# wifi_smart_controller.net
KiCad netlist of a schematic drawn in EasyEDA Pro
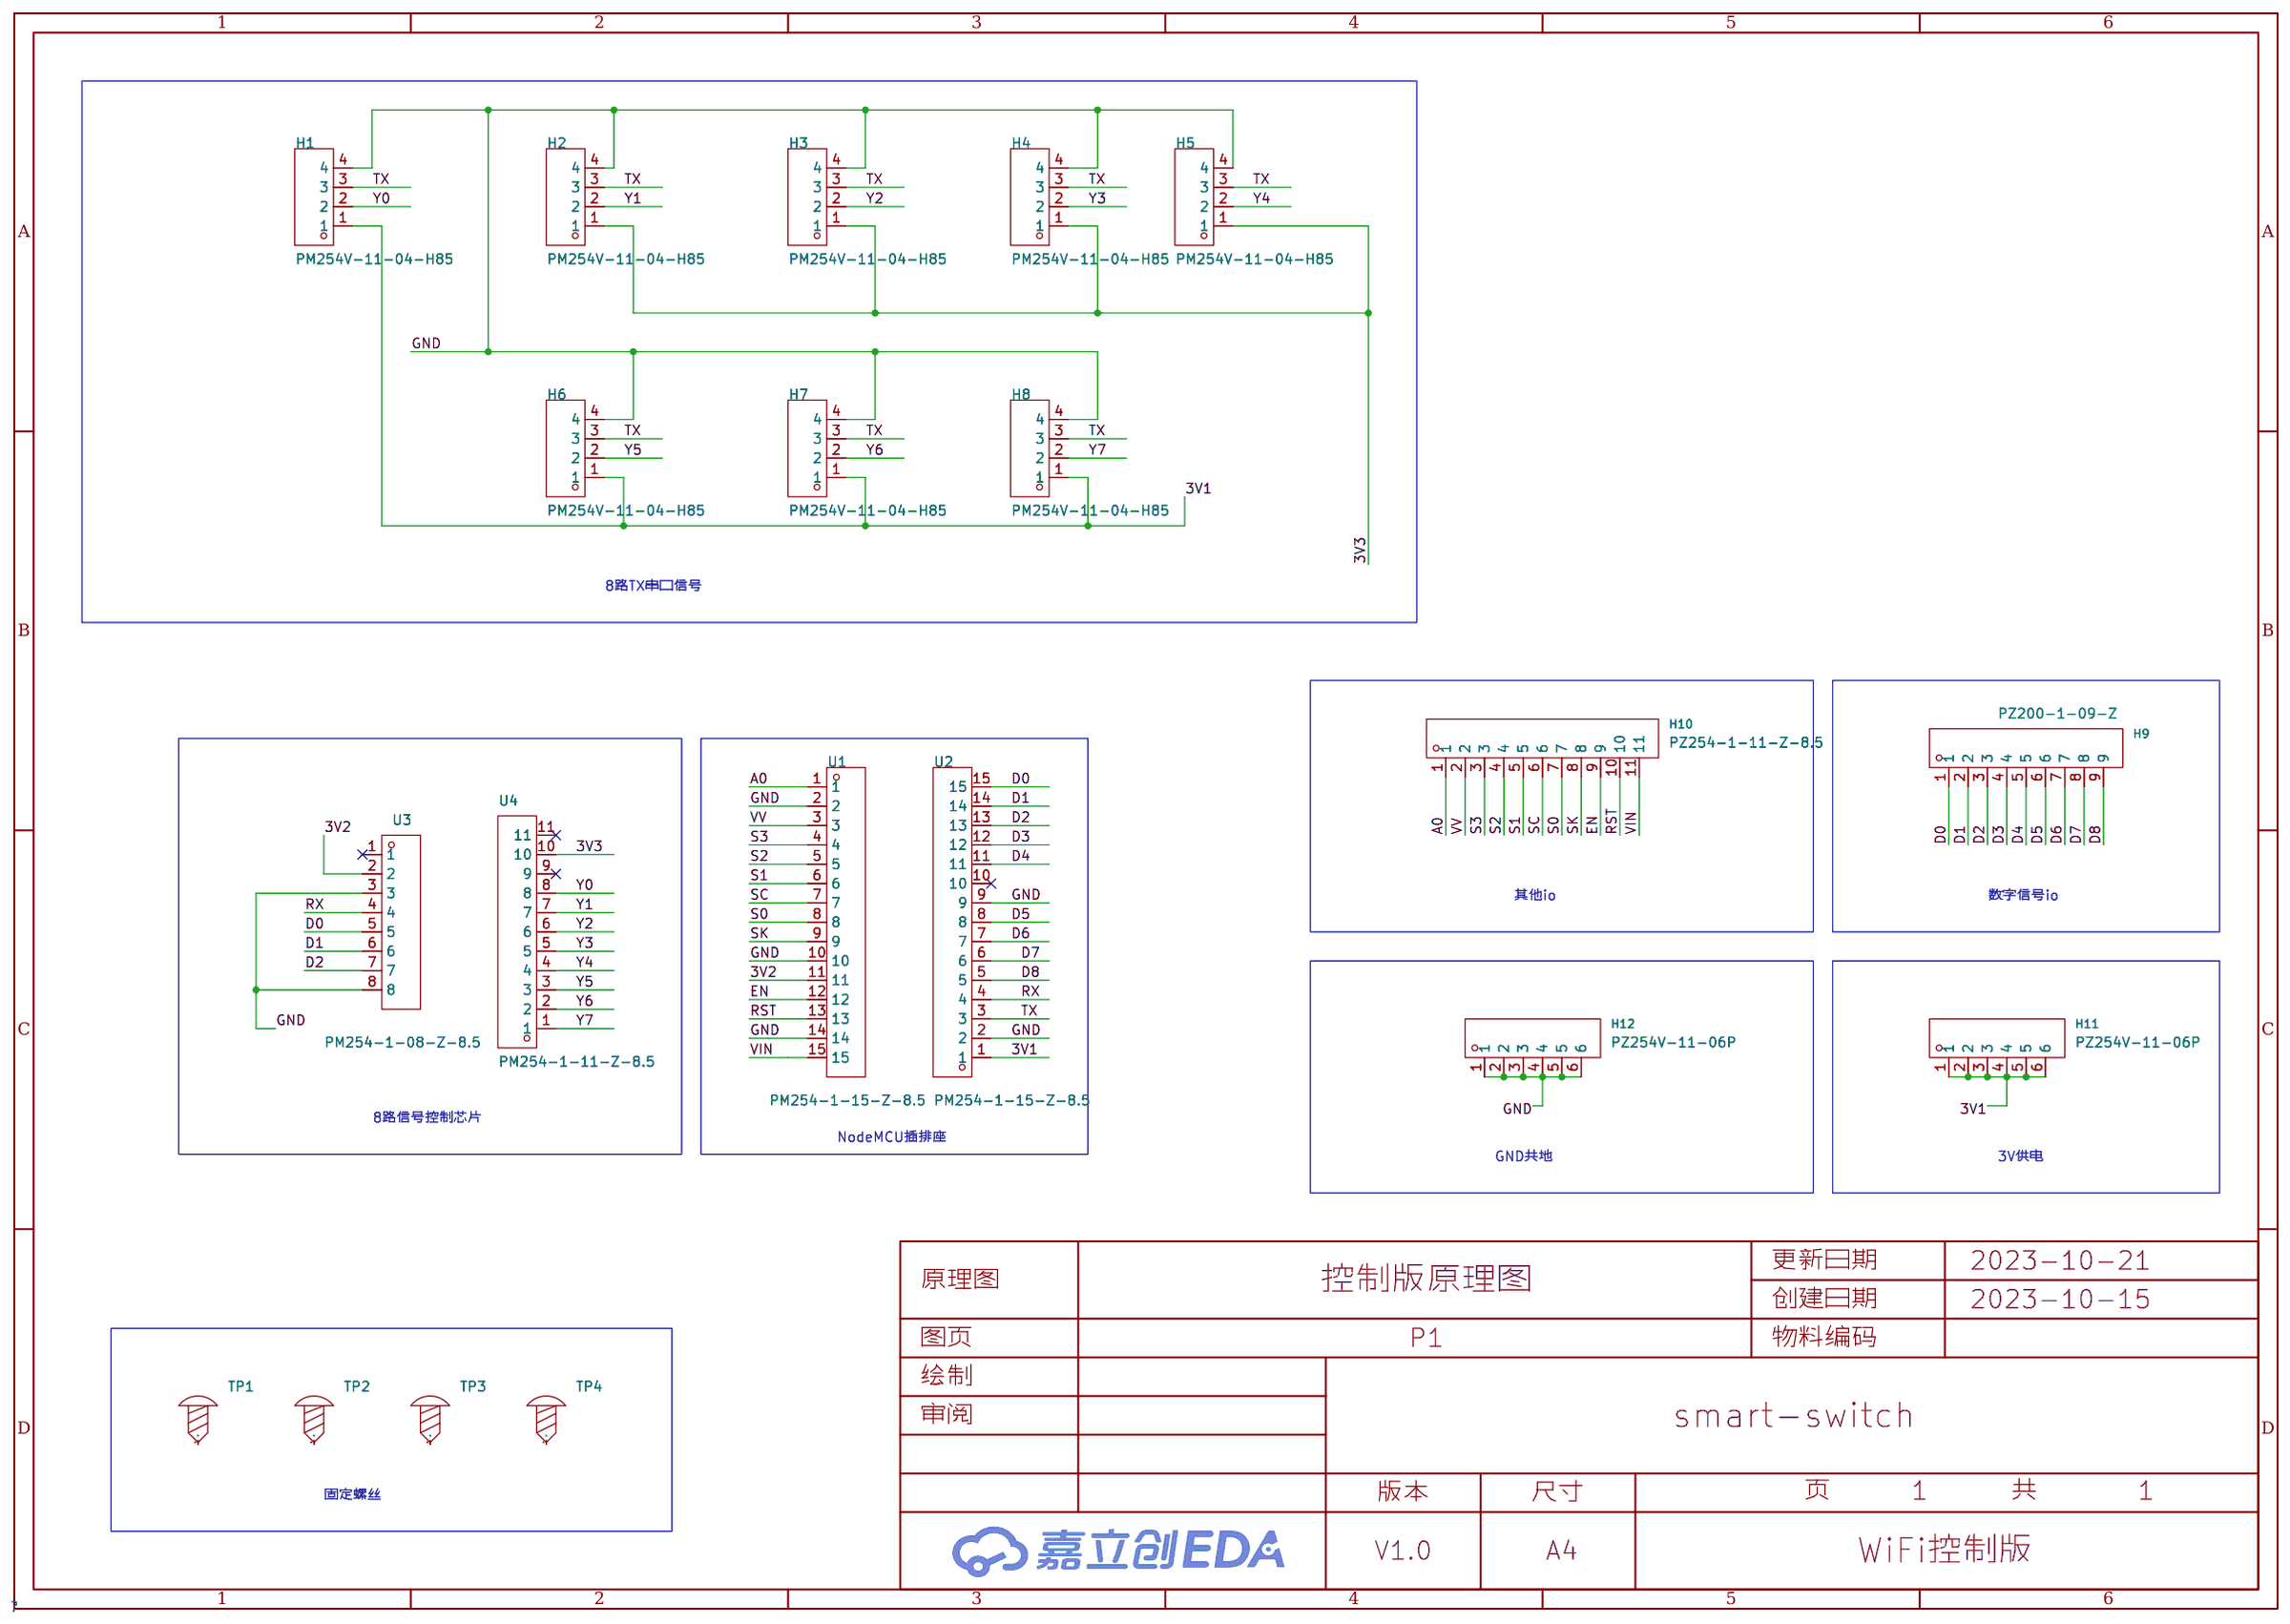
[diagram p0: schematic sheet]

(export (version "E")
  (design (tool "Eeschema 10.0.6"))
  (components
    (comp (ref "H1")
      (value "PM254V-11-04-H85")
      (footprint "easyedapro:HDR-TH_4P-P2.54-V-F")
      (description "排数:单排;总孔位数:4P;间距:2.54mm;插孔结构:1x4P;行距:-;安装类型:直插;塑高:-;触头材质:黄铜;触头镀层:-;")
      (fields (field (name "Manufacturer") "XFCN(兴飞)"))
      (libsource (lib "easyedapro") (part "PM254V-11-04-H85"))
    )
    (comp (ref "H2")
      (value "PM254V-11-04-H85")
      (footprint "easyedapro:HDR-TH_4P-P2.54-V-F")
      (description "排数:单排;总孔位数:4P;间距:2.54mm;插孔结构:1x4P;行距:-;安装类型:直插;塑高:-;触头材质:黄铜;触头镀层:-;")
      (fields (field (name "Manufacturer") "XFCN(兴飞)"))
      (libsource (lib "easyedapro") (part "PM254V-11-04-H85"))
    )
    (comp (ref "H3")
      (value "PM254V-11-04-H85")
      (footprint "easyedapro:HDR-TH_4P-P2.54-V-F")
      (description "排数:单排;总孔位数:4P;间距:2.54mm;插孔结构:1x4P;行距:-;安装类型:直插;塑高:-;触头材质:黄铜;触头镀层:-;")
      (fields (field (name "Manufacturer") "XFCN(兴飞)"))
      (libsource (lib "easyedapro") (part "PM254V-11-04-H85"))
    )
    (comp (ref "H4")
      (value "PM254V-11-04-H85")
      (footprint "easyedapro:HDR-TH_4P-P2.54-V-F")
      (description "排数:单排;总孔位数:4P;间距:2.54mm;插孔结构:1x4P;行距:-;安装类型:直插;塑高:-;触头材质:黄铜;触头镀层:-;")
      (fields (field (name "Manufacturer") "XFCN(兴飞)"))
      (libsource (lib "easyedapro") (part "PM254V-11-04-H85"))
    )
    (comp (ref "H5")
      (value "PM254V-11-04-H85")
      (footprint "easyedapro:HDR-TH_4P-P2.54-V-F")
      (description "排数:单排;总孔位数:4P;间距:2.54mm;插孔结构:1x4P;行距:-;安装类型:直插;塑高:-;触头材质:黄铜;触头镀层:-;")
      (fields (field (name "Manufacturer") "XFCN(兴飞)"))
      (libsource (lib "easyedapro") (part "PM254V-11-04-H85"))
    )
    (comp (ref "H6")
      (value "PM254V-11-04-H85")
      (footprint "easyedapro:HDR-TH_4P-P2.54-V-F")
      (description "排数:单排;总孔位数:4P;间距:2.54mm;插孔结构:1x4P;行距:-;安装类型:直插;塑高:-;触头材质:黄铜;触头镀层:-;")
      (fields (field (name "Manufacturer") "XFCN(兴飞)"))
      (libsource (lib "easyedapro") (part "PM254V-11-04-H85"))
    )
    (comp (ref "H7")
      (value "PM254V-11-04-H85")
      (footprint "easyedapro:HDR-TH_4P-P2.54-V-F")
      (description "排数:单排;总孔位数:4P;间距:2.54mm;插孔结构:1x4P;行距:-;安装类型:直插;塑高:-;触头材质:黄铜;触头镀层:-;")
      (fields (field (name "Manufacturer") "XFCN(兴飞)"))
      (libsource (lib "easyedapro") (part "PM254V-11-04-H85"))
    )
    (comp (ref "H8")
      (value "PM254V-11-04-H85")
      (footprint "easyedapro:HDR-TH_4P-P2.54-V-F")
      (description "排数:单排;总孔位数:4P;间距:2.54mm;插孔结构:1x4P;行距:-;安装类型:直插;塑高:-;触头材质:黄铜;触头镀层:-;")
      (fields (field (name "Manufacturer") "XFCN(兴飞)"))
      (libsource (lib "easyedapro") (part "PM254V-11-04-H85"))
    )
    (comp (ref "H9")
      (value "PZ200-1-09-Z")
      (footprint "easyedapro:HDR-TH_9P-P2.00-V-M")
      (fields (field (name "Manufacturer") "HCTL(华灿天禄)"))
      (libsource (lib "easyedapro") (part "PZ200-1-09-Z"))
    )
    (comp (ref "H10")
      (value "PZ254-1-11-Z-8.5")
      (footprint "easyedapro:HDR-TH_11P-P2.54-V-M")
      (fields (field (name "Manufacturer") "HCTL(华灿天禄)"))
      (libsource (lib "easyedapro") (part "PZ254-1-11-Z-8.5"))
    )
    (comp (ref "H11")
      (value "PZ254V-11-06P")
      (footprint "easyedapro:HDR-TH_6P-P2.54-V-M")
      (fields (field (name "Manufacturer") "XFCN(兴飞)"))
      (libsource (lib "easyedapro") (part "PZ254V-11-06P"))
    )
    (comp (ref "H12")
      (value "PZ254V-11-06P")
      (footprint "easyedapro:HDR-TH_6P-P2.54-V-M")
      (fields (field (name "Manufacturer") "XFCN(兴飞)"))
      (libsource (lib "easyedapro") (part "PZ254V-11-06P"))
    )
    (comp (ref "TP1") (value "~") (footprint "easyedapro:M2螺丝") (libsource (lib "easyedapro") (part "螺丝孔")))
    (comp (ref "TP2") (value "~") (footprint "easyedapro:M2螺丝") (libsource (lib "easyedapro") (part "螺丝孔")))
    (comp (ref "TP3") (value "~") (footprint "easyedapro:M2螺丝") (libsource (lib "easyedapro") (part "螺丝孔")))
    (comp (ref "TP4") (value "~") (footprint "easyedapro:M2螺丝") (libsource (lib "easyedapro") (part "螺丝孔")))
    (comp (ref "U1")
      (value "PM254-1-15-Z-8.5")
      (footprint "easyedapro:HDR-TH_15P-P2.54-V-F")
      (fields (field (name "Manufacturer") "HCTL(华灿天禄)"))
      (libsource (lib "easyedapro") (part "PM254-1-15-Z-8.5"))
    )
    (comp (ref "U2")
      (value "PM254-1-15-Z-8.5")
      (footprint "easyedapro:HDR-TH_15P-P2.54-V-F")
      (fields (field (name "Manufacturer") "HCTL(华灿天禄)"))
      (libsource (lib "easyedapro") (part "PM254-1-15-Z-8.5"))
    )
    (comp (ref "U3")
      (value "PM254-1-08-Z-8.5")
      (footprint "easyedapro:HDR-TH_8P-P2.54-V-F")
      (fields (field (name "Manufacturer") "HCTL(华灿天禄)"))
      (libsource (lib "easyedapro") (part "PM254-1-08-Z-8.5"))
    )
    (comp (ref "U4")
      (value "PM254-1-11-Z-8.5")
      (footprint "easyedapro:HDR-TH_11P-P2.54-V-F")
      (fields (field (name "Manufacturer") "HCTL(华灿天禄)"))
      (libsource (lib "easyedapro") (part "PM254-1-11-Z-8.5"))
    )
  )
  (nets
    (net (code "1") (name "/3V1") (class "Default")
      (node (ref "H1") (pin "1") (pinfunction "1_1") (pintype "unspecified"))
      (node (ref "H11") (pin "1") (pinfunction "1_1") (pintype "input"))
      (node (ref "H11") (pin "2") (pinfunction "2_2") (pintype "input"))
      (node (ref "H11") (pin "3") (pinfunction "3_3") (pintype "input"))
      (node (ref "H11") (pin "4") (pinfunction "4_4") (pintype "input"))
      (node (ref "H11") (pin "5") (pinfunction "5_5") (pintype "input"))
      (node (ref "H11") (pin "6") (pinfunction "6_6") (pintype "input"))
      (node (ref "H6") (pin "1") (pinfunction "1_1") (pintype "unspecified"))
      (node (ref "H7") (pin "1") (pinfunction "1_1") (pintype "unspecified"))
      (node (ref "H8") (pin "1") (pinfunction "1_1") (pintype "unspecified"))
      (node (ref "U2") (pin "1") (pinfunction "1_1") (pintype "unspecified"))
    )
    (net (code "2") (name "/3V2") (class "Default")
      (node (ref "U1") (pin "11") (pinfunction "11_11") (pintype "unspecified"))
      (node (ref "U3") (pin "2") (pinfunction "2_2") (pintype "unspecified"))
    )
    (net (code "3") (name "/3V3") (class "Default")
      (node (ref "H2") (pin "1") (pinfunction "1_1") (pintype "unspecified"))
      (node (ref "H3") (pin "1") (pinfunction "1_1") (pintype "unspecified"))
      (node (ref "H4") (pin "1") (pinfunction "1_1") (pintype "unspecified"))
      (node (ref "H5") (pin "1") (pinfunction "1_1") (pintype "unspecified"))
      (node (ref "U4") (pin "10") (pinfunction "10_10") (pintype "unspecified"))
    )
    (net (code "4") (name "/A0") (class "Default")
      (node (ref "H10") (pin "1") (pinfunction "1_1") (pintype "input"))
      (node (ref "U1") (pin "1") (pinfunction "1_1") (pintype "unspecified"))
    )
    (net (code "5") (name "/D0") (class "Default")
      (node (ref "H9") (pin "1") (pinfunction "1_1") (pintype "input"))
      (node (ref "U2") (pin "15") (pinfunction "15_15") (pintype "unspecified"))
      (node (ref "U3") (pin "5") (pinfunction "5_5") (pintype "unspecified"))
    )
    (net (code "6") (name "/D1") (class "Default")
      (node (ref "H9") (pin "2") (pinfunction "2_2") (pintype "input"))
      (node (ref "U2") (pin "14") (pinfunction "14_14") (pintype "unspecified"))
      (node (ref "U3") (pin "6") (pinfunction "6_6") (pintype "unspecified"))
    )
    (net (code "7") (name "/D2") (class "Default")
      (node (ref "H9") (pin "3") (pinfunction "3_3") (pintype "input"))
      (node (ref "U2") (pin "13") (pinfunction "13_13") (pintype "unspecified"))
      (node (ref "U3") (pin "7") (pinfunction "7_7") (pintype "unspecified"))
    )
    (net (code "8") (name "/D3") (class "Default")
      (node (ref "H9") (pin "4") (pinfunction "4_4") (pintype "input"))
      (node (ref "U2") (pin "12") (pinfunction "12_12") (pintype "unspecified"))
    )
    (net (code "9") (name "/D4") (class "Default")
      (node (ref "H9") (pin "5") (pinfunction "5_5") (pintype "input"))
      (node (ref "U2") (pin "11") (pinfunction "11_11") (pintype "unspecified"))
    )
    (net (code "10") (name "/D5") (class "Default")
      (node (ref "H9") (pin "6") (pinfunction "6_6") (pintype "input"))
      (node (ref "U2") (pin "8") (pinfunction "8_8") (pintype "unspecified"))
    )
    (net (code "11") (name "/D6") (class "Default")
      (node (ref "H9") (pin "7") (pinfunction "7_7") (pintype "input"))
      (node (ref "U2") (pin "7") (pinfunction "7_7") (pintype "unspecified"))
    )
    (net (code "12") (name "/D7") (class "Default")
      (node (ref "H9") (pin "8") (pinfunction "8_8") (pintype "input"))
      (node (ref "U2") (pin "6") (pinfunction "6_6") (pintype "unspecified"))
    )
    (net (code "13") (name "/D8") (class "Default")
      (node (ref "H9") (pin "9") (pinfunction "9_9") (pintype "input"))
      (node (ref "U2") (pin "5") (pinfunction "5_5") (pintype "unspecified"))
    )
    (net (code "14") (name "/EN") (class "Default")
      (node (ref "H10") (pin "9") (pinfunction "9_9") (pintype "input"))
      (node (ref "U1") (pin "12") (pinfunction "12_12") (pintype "unspecified"))
    )
    (net (code "15") (name "/GND") (class "Default")
      (node (ref "H1") (pin "4") (pinfunction "4_4") (pintype "unspecified"))
      (node (ref "H12") (pin "1") (pinfunction "1_1") (pintype "input"))
      (node (ref "H12") (pin "2") (pinfunction "2_2") (pintype "input"))
      (node (ref "H12") (pin "3") (pinfunction "3_3") (pintype "input"))
      (node (ref "H12") (pin "4") (pinfunction "4_4") (pintype "input"))
      (node (ref "H12") (pin "5") (pinfunction "5_5") (pintype "input"))
      (node (ref "H12") (pin "6") (pinfunction "6_6") (pintype "input"))
      (node (ref "H2") (pin "4") (pinfunction "4_4") (pintype "unspecified"))
      (node (ref "H3") (pin "4") (pinfunction "4_4") (pintype "unspecified"))
      (node (ref "H4") (pin "4") (pinfunction "4_4") (pintype "unspecified"))
      (node (ref "H5") (pin "4") (pinfunction "4_4") (pintype "unspecified"))
      (node (ref "H6") (pin "4") (pinfunction "4_4") (pintype "unspecified"))
      (node (ref "H7") (pin "4") (pinfunction "4_4") (pintype "unspecified"))
      (node (ref "H8") (pin "4") (pinfunction "4_4") (pintype "unspecified"))
      (node (ref "U1") (pin "10") (pinfunction "10_10") (pintype "unspecified"))
      (node (ref "U1") (pin "14") (pinfunction "14_14") (pintype "unspecified"))
      (node (ref "U1") (pin "2") (pinfunction "2_2") (pintype "unspecified"))
      (node (ref "U2") (pin "2") (pinfunction "2_2") (pintype "unspecified"))
      (node (ref "U2") (pin "9") (pinfunction "9_9") (pintype "unspecified"))
      (node (ref "U3") (pin "3") (pinfunction "3_3") (pintype "unspecified"))
      (node (ref "U3") (pin "8") (pinfunction "8_8") (pintype "unspecified"))
    )
    (net (code "16") (name "/RST") (class "Default")
      (node (ref "H10") (pin "10") (pinfunction "10_10") (pintype "input"))
      (node (ref "U1") (pin "13") (pinfunction "13_13") (pintype "unspecified"))
    )
    (net (code "17") (name "/RX") (class "Default")
      (node (ref "U2") (pin "4") (pinfunction "4_4") (pintype "unspecified"))
      (node (ref "U3") (pin "4") (pinfunction "4_4") (pintype "unspecified"))
    )
    (net (code "18") (name "/S0") (class "Default")
      (node (ref "H10") (pin "7") (pinfunction "7_7") (pintype "input"))
      (node (ref "U1") (pin "8") (pinfunction "8_8") (pintype "unspecified"))
    )
    (net (code "19") (name "/S1") (class "Default")
      (node (ref "H10") (pin "5") (pinfunction "5_5") (pintype "input"))
      (node (ref "U1") (pin "6") (pinfunction "6_6") (pintype "unspecified"))
    )
    (net (code "20") (name "/S2") (class "Default")
      (node (ref "H10") (pin "4") (pinfunction "4_4") (pintype "input"))
      (node (ref "U1") (pin "5") (pinfunction "5_5") (pintype "unspecified"))
    )
    (net (code "21") (name "/S3") (class "Default")
      (node (ref "H10") (pin "3") (pinfunction "3_3") (pintype "input"))
      (node (ref "U1") (pin "4") (pinfunction "4_4") (pintype "unspecified"))
    )
    (net (code "22") (name "/SC") (class "Default")
      (node (ref "H10") (pin "6") (pinfunction "6_6") (pintype "input"))
      (node (ref "U1") (pin "7") (pinfunction "7_7") (pintype "unspecified"))
    )
    (net (code "23") (name "/SK") (class "Default")
      (node (ref "H10") (pin "8") (pinfunction "8_8") (pintype "input"))
      (node (ref "U1") (pin "9") (pinfunction "9_9") (pintype "unspecified"))
    )
    (net (code "24") (name "/TX") (class "Default")
      (node (ref "H1") (pin "3") (pinfunction "3_3") (pintype "unspecified"))
      (node (ref "H2") (pin "3") (pinfunction "3_3") (pintype "unspecified"))
      (node (ref "H3") (pin "3") (pinfunction "3_3") (pintype "unspecified"))
      (node (ref "H4") (pin "3") (pinfunction "3_3") (pintype "unspecified"))
      (node (ref "H5") (pin "3") (pinfunction "3_3") (pintype "unspecified"))
      (node (ref "H6") (pin "3") (pinfunction "3_3") (pintype "unspecified"))
      (node (ref "H7") (pin "3") (pinfunction "3_3") (pintype "unspecified"))
      (node (ref "H8") (pin "3") (pinfunction "3_3") (pintype "unspecified"))
      (node (ref "U2") (pin "3") (pinfunction "3_3") (pintype "unspecified"))
    )
    (net (code "25") (name "/VIN") (class "Default")
      (node (ref "H10") (pin "11") (pinfunction "11_11") (pintype "input"))
      (node (ref "U1") (pin "15") (pinfunction "15_15") (pintype "unspecified"))
    )
    (net (code "26") (name "/VV") (class "Default")
      (node (ref "H10") (pin "2") (pinfunction "2_2") (pintype "input"))
      (node (ref "U1") (pin "3") (pinfunction "3_3") (pintype "unspecified"))
    )
    (net (code "27") (name "/Y0") (class "Default")
      (node (ref "H1") (pin "2") (pinfunction "2_2") (pintype "unspecified"))
      (node (ref "U4") (pin "8") (pinfunction "8_8") (pintype "unspecified"))
    )
    (net (code "28") (name "/Y1") (class "Default")
      (node (ref "H2") (pin "2") (pinfunction "2_2") (pintype "unspecified"))
      (node (ref "U4") (pin "7") (pinfunction "7_7") (pintype "unspecified"))
    )
    (net (code "29") (name "/Y2") (class "Default")
      (node (ref "H3") (pin "2") (pinfunction "2_2") (pintype "unspecified"))
      (node (ref "U4") (pin "6") (pinfunction "6_6") (pintype "unspecified"))
    )
    (net (code "30") (name "/Y3") (class "Default")
      (node (ref "H4") (pin "2") (pinfunction "2_2") (pintype "unspecified"))
      (node (ref "U4") (pin "5") (pinfunction "5_5") (pintype "unspecified"))
    )
    (net (code "31") (name "/Y4") (class "Default")
      (node (ref "H5") (pin "2") (pinfunction "2_2") (pintype "unspecified"))
      (node (ref "U4") (pin "4") (pinfunction "4_4") (pintype "unspecified"))
    )
    (net (code "32") (name "/Y5") (class "Default")
      (node (ref "H6") (pin "2") (pinfunction "2_2") (pintype "unspecified"))
      (node (ref "U4") (pin "3") (pinfunction "3_3") (pintype "unspecified"))
    )
    (net (code "33") (name "/Y6") (class "Default")
      (node (ref "H7") (pin "2") (pinfunction "2_2") (pintype "unspecified"))
      (node (ref "U4") (pin "2") (pinfunction "2_2") (pintype "unspecified"))
    )
    (net (code "34") (name "/Y7") (class "Default")
      (node (ref "H8") (pin "2") (pinfunction "2_2") (pintype "unspecified"))
      (node (ref "U4") (pin "1") (pinfunction "1_1") (pintype "unspecified"))
    )
    (net (code "35") (name "unconnected-(TP1-Pad1)") (class "Default")
      (node (ref "TP1") (pin "1") (pinfunction "1_1") (pintype "input"))
    )
    (net (code "36") (name "unconnected-(TP2-Pad1)") (class "Default")
      (node (ref "TP2") (pin "1") (pinfunction "1_1") (pintype "input"))
    )
    (net (code "37") (name "unconnected-(TP3-Pad1)") (class "Default")
      (node (ref "TP3") (pin "1") (pinfunction "1_1") (pintype "input"))
    )
    (net (code "38") (name "unconnected-(TP4-Pad1)") (class "Default")
      (node (ref "TP4") (pin "1") (pinfunction "1_1") (pintype "input"))
    )
    (net (code "39") (name "unconnected-(U2-Pad10)") (class "Default")
      (node (ref "U2") (pin "10") (pinfunction "10_10") (pintype "unspecified+no_connect"))
    )
    (net (code "40") (name "unconnected-(U3-Pad1)") (class "Default")
      (node (ref "U3") (pin "1") (pinfunction "1_1") (pintype "unspecified+no_connect"))
    )
    (net (code "41") (name "unconnected-(U4-Pad9)") (class "Default")
      (node (ref "U4") (pin "9") (pinfunction "9_9") (pintype "unspecified+no_connect"))
    )
    (net (code "42") (name "unconnected-(U4-Pad11)") (class "Default")
      (node (ref "U4") (pin "11") (pinfunction "11_11") (pintype "unspecified+no_connect"))
    )
  )
)
